# Carrierboard.net
KiCad netlist of a schematic drawn in Altium Designer
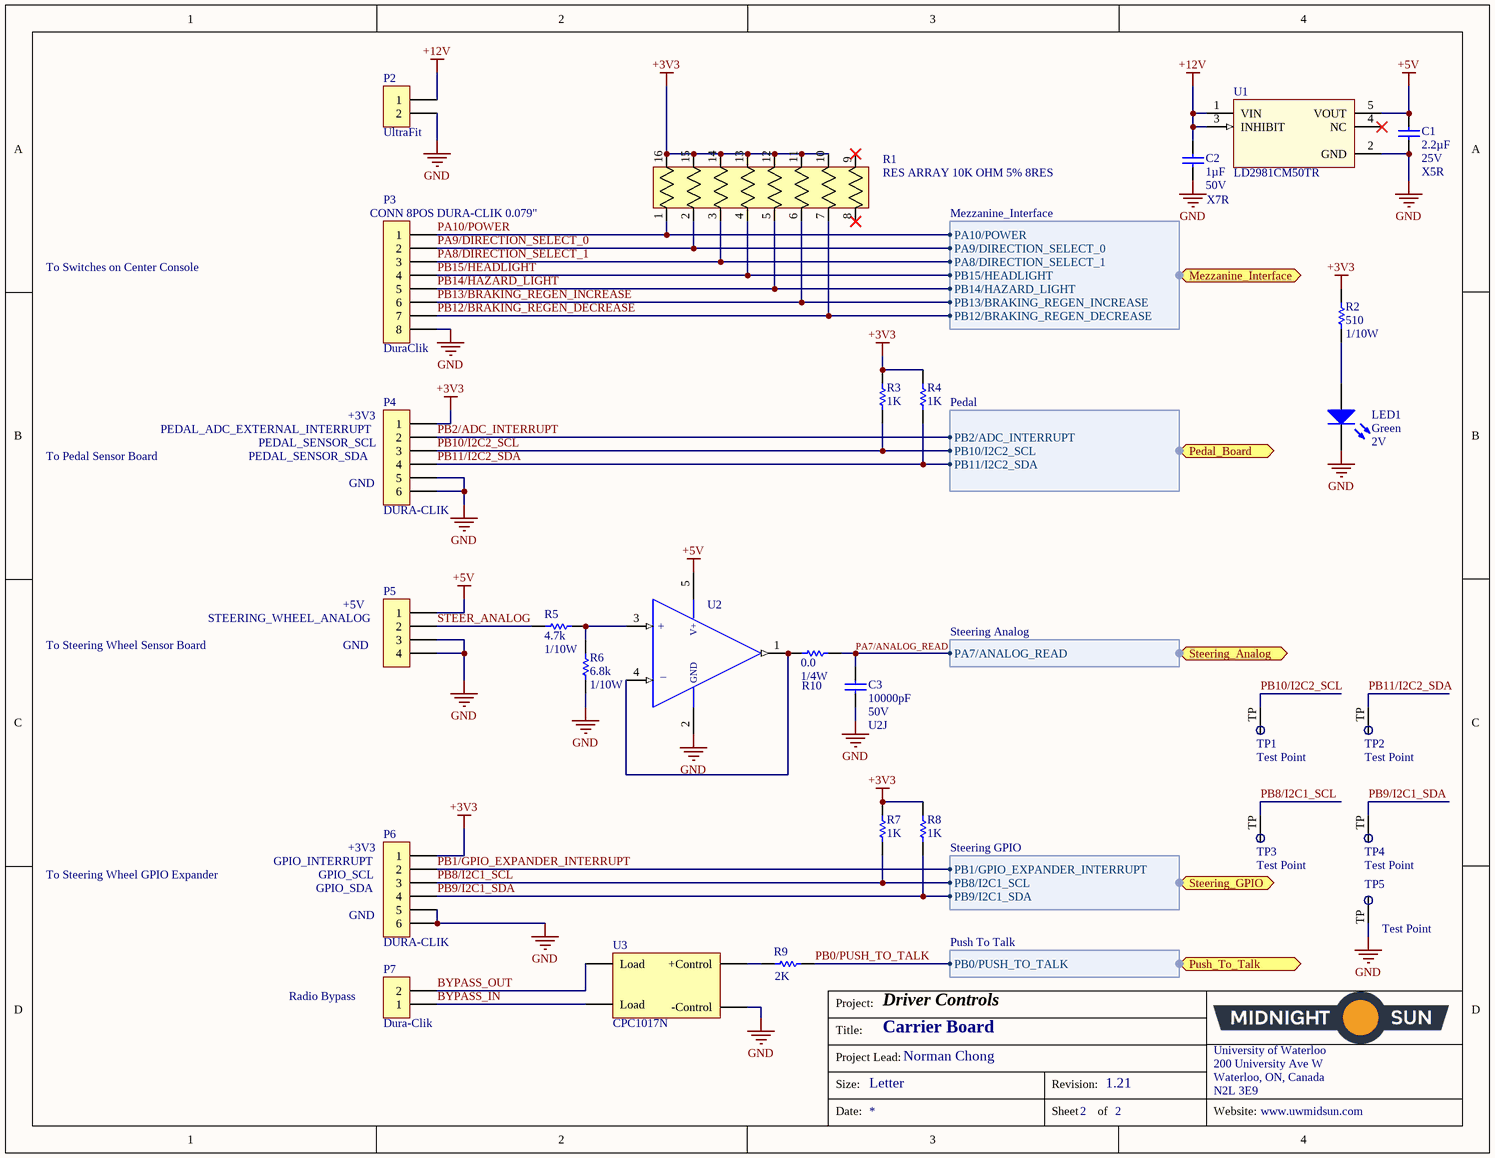
[diagram p0: Carrierboard.SchDoc]

(export (version "E")
  (design (tool "Eeschema 10.0.6"))
  (components
    (comp (ref "C1")
      (value "CAP CER 2.2UF 25V 10% X5R 0603")
      (footprint "CAP, 0603")
      (description "2.2µF ±10% 25V Ceramic Capacitor X5R 0603 (1608 Metric)")
      (fields
        (field (name "TOLERANCE") "±10%")
        (field (name "CAPACITANCE") "2.2µF")
        (field (name "VOLTAGE") "25V")
        (field (name "TEMPERATURE COEFFICIENT") "X5R")
      )
      (libsource (lib "Schematic Diagrams") (part "CAP CER 2.2UF 25V 10% X5R 0603"))
    )
    (comp (ref "C2")
      (value "CAP CER 1UF 50V 10% X7R 0603")
      (footprint "CAP, 0603")
      (description "1µF ±10% 50V Ceramic Capacitor X7R 0603 (1608 Metric)")
      (fields
        (field (name "TOLERANCE") "±10%")
        (field (name "CAPACITANCE") "1µF")
        (field (name "VOLTAGE") "50V")
        (field (name "TEMPERATURE COEFFICIENT") "X7R")
      )
      (libsource (lib "Schematic Diagrams") (part "CAP CER 1UF 50V 10% X7R 0603"))
    )
    (comp (ref "C3")
      (value "CAP CER 10nF 50V 5% X7R 0603")
      (footprint "CAP, 0603")
      (description "10000pF ±5% 50V Ceramic Capacitor U2J 0603 (1608 Metric)")
      (fields
        (field (name "TOLERANCE") "±5%")
        (field (name "CAPACITANCE") "10000pF")
        (field (name "VOLTAGE") "50V")
        (field (name "TEMPERATURE COEFFICIENT") "U2J")
      )
      (libsource (lib "Schematic Diagrams") (part "CAP CER 10nF 50V 5% X7R 0603"))
    )
    (comp (ref "LED1")
      (value "LED GREEN CLEAR 2V 0603")
      (footprint "LED_0603")
      (description "Green 572nm LED Indication - Discrete 2V 0603 (1608 Metric)")
      (fields
        (field (name "MANUFACTURER") "Wurth Electronics Inc.")
        (field (name "MANUFACTURER PART NUMBER") "150060VS75000")
        (field (name "COLOR") "Green")
        (field (name "VOLTAGE - FORWARD (VF) (TYP)") "2V")
      )
      (libsource (lib "Schematic Diagrams") (part "LED GREEN CLEAR 2V 0603"))
    )
    (comp (ref "P2")
      (value "CONN 2POS ULTRA-FIT 0.138\"")
      (footprint "CONN, 2POS ULTRA-FIT")
      (description "2 Positions Header, Shrouded Connector 0.138\" (3.50mm) Through Hole Gold")
      (fields (field (name "VOLTAGE") "400V") (field (name "SERIES") "UltraFit"))
      (libsource (lib "Schematic Diagrams") (part "CONN 2POS ULTRA-FIT 0.138{dblquote}"))
    )
    (comp (ref "P3")
      (value "CONN 8POS DURA-CLIK 0.079\"")
      (footprint "CONN, 8POS Dura-Clik")
      (description "8 Positions Header Connector 0.079\" (2.00mm) Surface Mount Tin")
      (fields (field (name "SERIES") "DuraClik"))
      (libsource (lib "Schematic Diagrams") (part "CONN 8POS DURA-CLIK 0.079{dblquote}"))
    )
    (comp (ref "P4")
      (value "DURA-CLIK")
      (footprint "CONN, 6POS DURA-CLIK VERT")
      (description "6 Positions Header, Shrouded Connector 0.079\" (2.00mm) Surface Mount, Vertical Tin")
      (fields (field (name "MANUFACTURER") "Molex") (field (name "MANUFACTURER PART NUMBER") "5600200820"))
      (libsource (lib "Schematic Diagrams") (part "CONN 6POS DURA-CLIK 0.079{dblquote}"))
    )
    (comp (ref "P5")
      (value "Dura-Clik")
      (footprint "CONN, 4POS DURA-CLIK VERT")
      (description "4 Positions Header Connector 0.079\" (2.00mm) Surface Mount Tin")
      (fields
        (field (name "MANUFACTURER") "Molex, LLC")
        (field (name "MANUFACTURER PART NUMBER") "5600200420")
      )
      (libsource (lib "Schematic Diagrams") (part "CONN 4POS DURA-CLIK 0.079{dblquote}"))
    )
    (comp (ref "P6")
      (value "DURA-CLIK")
      (footprint "CONN, 6POS DURA-CLIK VERT")
      (description "6 Positions Header, Shrouded Connector 0.079\" (2.00mm) Surface Mount, Vertical Tin")
      (fields (field (name "MANUFACTURER") "Molex") (field (name "MANUFACTURER PART NUMBER") "5600200820"))
      (libsource (lib "Schematic Diagrams") (part "CONN 6POS DURA-CLIK 0.079{dblquote}"))
    )
    (comp (ref "P7")
      (value "Dura-Clik")
      (footprint "CONN, 2POS Dura-Click Vertical")
      (description "2 Positions Header, Shrouded Connector 0.079\" (2.00mm) Surface Mount, Vertical Tin")
      (fields
        (field (name "MANUFACTURER") "Molex, LLC")
        (field (name "MANUFACTURER PART NUMBER") "5600200220")
      )
      (libsource (lib "Schematic Diagrams") (part "CONN 2POS DURA-CLIK 0.079{dblquote} VERT"))
    )
    (comp (ref "R1")
      (value "RES ARRAY 10K OHM 5% 8RES")
      (footprint "RES ARRAY, 8 POS 1506")
      (description "RES ARRAY SMD 10K 5% 62.5mW 1506")
      (fields
        (field (name "MANUFACTURER_PART_NUMBER") "EXB-2HV103JV")
        (field (name "MANUFACTURER") "Panasonic Electronic Components")
        (field (name "COPYRIGHT") "Copyright (C) 2015 Accelerated Designs. All rights reserved")
      )
      (libsource (lib "Schematic Diagrams") (part "RES ARRAY 10K OHM 5% 8RES EXB-2HV103JV"))
    )
    (comp (ref "R2")
      (value "RES 510 OHM 5% 1/10W 0603")
      (footprint "RES, 0603")
      (description "RES SMD 510 OHM 5% 1/10W 0603")
      (fields
        (field (name "TOLERANCE") "±5%")
        (field (name "RESISTANCE") "510")
        (field (name "POWER") "1/10W")
      )
      (libsource (lib "Schematic Diagrams") (part "RES 510 OHM 5% 1/10W 0603"))
    )
    (comp (ref "R3")
      (value "1K")
      (footprint "RES, 0603")
      (description "1k Ohm ±5% 0.1W, 1/10W Chip Resistor 0603 (1608 Metric)")
      (fields
        (field (name "MANUFACTURER") "Yageo")
        (field (name "MANUFACTURER PART NUMBER") "RC0603JR-071KL")
      )
      (libsource (lib "Schematic Diagrams") (part "RES 1K OHM 5% 1/10W 0603"))
    )
    (comp (ref "R4")
      (value "1K")
      (footprint "RES, 0603")
      (description "1k Ohm ±5% 0.1W, 1/10W Chip Resistor 0603 (1608 Metric)")
      (fields
        (field (name "MANUFACTURER") "Yageo")
        (field (name "MANUFACTURER PART NUMBER") "RC0603JR-071KL")
      )
      (libsource (lib "Schematic Diagrams") (part "RES 1K OHM 5% 1/10W 0603"))
    )
    (comp (ref "R5")
      (value "RES 4.7K OHM 1% 1/10W 0603")
      (footprint "RES, 0603")
      (description "4.7k Ohm ±1% 0.1W, 1/10W Chip Resistor 0603 (1608 Metric) Moisture Resistant Thick Film")
      (fields
        (field (name "TOLERANCE") "±1%")
        (field (name "RESISTANCE (OHMS)") "4.7k")
        (field (name "POWER (WATTS)") "1/10W")
      )
      (libsource (lib "Schematic Diagrams") (part "RES 4.7K OHM 1% 1/10W 0603"))
    )
    (comp (ref "R6")
      (value "RES 6.8k OHM 1% 1/10W 0603")
      (footprint "RES, 0603")
      (description "RES SMD 6.8K OHM 1% 1/10W 0603")
      (fields
        (field (name "TOLERANCE") "±1%")
        (field (name "RESISTANCE") "6.8k")
        (field (name "POWER") "1/10W")
      )
      (libsource (lib "Schematic Diagrams") (part "RES 6.8k OHM 1% 1/10W 0603"))
    )
    (comp (ref "R7")
      (value "1K")
      (footprint "RES, 0603")
      (description "1k Ohm ±5% 0.1W, 1/10W Chip Resistor 0603 (1608 Metric)")
      (fields
        (field (name "MANUFACTURER") "Yageo")
        (field (name "MANUFACTURER PART NUMBER") "RC0603JR-071KL")
      )
      (libsource (lib "Schematic Diagrams") (part "RES 1K OHM 5% 1/10W 0603"))
    )
    (comp (ref "R8")
      (value "1K")
      (footprint "RES, 0603")
      (description "1k Ohm ±5% 0.1W, 1/10W Chip Resistor 0603 (1608 Metric)")
      (fields
        (field (name "MANUFACTURER") "Yageo")
        (field (name "MANUFACTURER PART NUMBER") "RC0603JR-071KL")
      )
      (libsource (lib "Schematic Diagrams") (part "RES 1K OHM 5% 1/10W 0603"))
    )
    (comp (ref "R9")
      (value "2K")
      (footprint "RES, 0603")
      (description "2k Ohm ±1% 0.1W, 1/10W Chip Resistor 0603 (1608 Metric) Moisture Resistant Thick Film")
      (fields
        (field (name "MANUFACTURER") "Yageo")
        (field (name "MANUFACTURER PART NUMBER") "RC0603FR-072KL")
      )
      (libsource (lib "Schematic Diagrams") (part "RES 2K OHM 1% 1/10W 0603"))
    )
    (comp (ref "R10")
      (value "RES 0.0 OHM 1/4W 0603")
      (footprint "RES, 0603")
      (description "RES SMD 0.0 OHM JUMPER 1/4W 0603")
      (fields (field (name "RESISTANCE") "0.0") (field (name "POWER (WATTS)") "1/4W"))
      (libsource (lib "Schematic Diagrams") (part "RES 0.0 OHM 1/4W 0603"))
    )
    (comp (ref "TP1")
      (value "Test Point")
      (footprint "Test Point")
      (libsource (lib "Schematic Diagrams") (part "Test Point"))
    )
    (comp (ref "TP2")
      (value "Test Point")
      (footprint "Test Point")
      (libsource (lib "Schematic Diagrams") (part "Test Point"))
    )
    (comp (ref "TP3")
      (value "Test Point")
      (footprint "Test Point")
      (libsource (lib "Schematic Diagrams") (part "Test Point"))
    )
    (comp (ref "TP4")
      (value "Test Point")
      (footprint "Test Point")
      (libsource (lib "Schematic Diagrams") (part "Test Point"))
    )
    (comp (ref "TP5")
      (value "Test Point")
      (footprint "Test Point")
      (libsource (lib "Schematic Diagrams") (part "Test Point"))
    )
    (comp (ref "U1")
      (value "IC REG LDO 5V 0.1A SOT23-5")
      (footprint "SOT95P280X145-5N")
      (description "Linear Voltage Regulator IC Positive Fixed Output 5V 100mA SOT-23-5")
      (fields (field (name "MANUFACTURER PART NUMBER 1") "LD2981CM50TR"))
      (libsource (lib "Schematic Diagrams") (part "IC REG LDO 5V 0.1A SOT23-5"))
    )
    (comp (ref "U2")
      (value "IC OP AMP GEN PURPOSE RR 10MHZ SOT-23-5")
      (footprint "IC OP AMP GP RR 10MHZ SOT-23-5")
      (description "General Purpose Amplifier 1 Circuit Rail-to-Rail SOT-23-5")
      (libsource (lib "Schematic Diagrams") (part "IC OP AMP GEN PURPOSE RR 10MHZ SOT-23-5"))
    )
    (comp (ref "U3")
      (value "CPC1017N")
      (footprint "RELAY SOP4")
      (description "Relay Solid-State SPST-NO 4-SOP")
      (fields
        (field (name "MANUFACTURER") "IXYS Integrated Circuits Division")
        (field (name "MANUFACTURER PART NUMBER") "CPC1017NTR")
      )
      (libsource (lib "Schematic Diagrams") (part "RELAY CPC1017N SPST 100mA"))
    )
  )
  (nets
    (net (code "9") (name "+3V3") (class "Default")
      (node (ref "P4") (pin "1") (pinfunction "1_1") (pintype "passive"))
      (node (ref "P6") (pin "1") (pinfunction "1_1") (pintype "passive"))
      (node (ref "R1") (pin "10") (pinfunction "10_10") (pintype "passive"))
      (node (ref "R1") (pin "11") (pinfunction "11_11") (pintype "passive"))
      (node (ref "R1") (pin "12") (pinfunction "12_12") (pintype "passive"))
      (node (ref "R1") (pin "13") (pinfunction "13_13") (pintype "passive"))
      (node (ref "R1") (pin "14") (pinfunction "14_14") (pintype "passive"))
      (node (ref "R1") (pin "15") (pinfunction "15_15") (pintype "passive"))
      (node (ref "R1") (pin "16") (pinfunction "16_16") (pintype "passive"))
      (node (ref "R2") (pin "1") (pinfunction "1_1") (pintype "passive"))
      (node (ref "R3") (pin "1") (pinfunction "1_1") (pintype "passive"))
      (node (ref "R4") (pin "1") (pinfunction "1_1") (pintype "passive"))
      (node (ref "R7") (pin "1") (pinfunction "1_1") (pintype "passive"))
      (node (ref "R8") (pin "1") (pinfunction "1_1") (pintype "passive"))
    )
    (net (code "10") (name "+5V") (class "Default")
      (node (ref "C1") (pin "1") (pinfunction "1_1") (pintype "passive"))
      (node (ref "P5") (pin "1") (pinfunction "1_1") (pintype "passive"))
      (node (ref "U1") (pin "5") (pinfunction "VOUT_5") (pintype "power_in"))
      (node (ref "U2") (pin "5") (pinfunction "VDD_5") (pintype "power_in"))
    )
    (net (code "11") (name "+12V") (class "Default")
      (node (ref "C2") (pin "1") (pinfunction "1_1") (pintype "passive"))
      (node (ref "P2") (pin "1") (pinfunction "1_1") (pintype "passive"))
      (node (ref "U1") (pin "1") (pinfunction "VIN_1") (pintype "power_in"))
      (node (ref "U1") (pin "3") (pinfunction "INHIBIT_3") (pintype "input"))
    )
    (net (code "12") (name "/BYPASS_IN") (class "Default")
      (node (ref "P7") (pin "1") (pinfunction "1_1") (pintype "passive"))
      (node (ref "U3") (pin "3") (pinfunction "Load_3") (pintype "passive"))
    )
    (net (code "13") (name "/BYPASS_OUT") (class "Default")
      (node (ref "P7") (pin "2") (pinfunction "2_2") (pintype "passive"))
      (node (ref "U3") (pin "4") (pinfunction "Load_4") (pintype "passive"))
    )
    (net (code "14") (name "/PA7{slash}ANALOG_READ") (class "Default")
      (node (ref "C3") (pin "1") (pinfunction "1_1") (pintype "passive"))
      (node (ref "R10") (pin "2") (pinfunction "2_2") (pintype "passive"))
    )
    (net (code "15") (name "/PA8{slash}DIRECTION_SELECT_1") (class "Default")
      (node (ref "P3") (pin "3") (pinfunction "3_3") (pintype "passive"))
      (node (ref "R1") (pin "3") (pinfunction "3_3") (pintype "passive"))
    )
    (net (code "16") (name "/PA9{slash}DIRECTION_SELECT_0") (class "Default")
      (node (ref "P3") (pin "2") (pinfunction "2_2") (pintype "passive"))
      (node (ref "R1") (pin "2") (pinfunction "2_2") (pintype "passive"))
    )
    (net (code "17") (name "/PA10{slash}POWER") (class "Default")
      (node (ref "P3") (pin "1") (pinfunction "1_1") (pintype "passive"))
      (node (ref "R1") (pin "1") (pinfunction "1_1") (pintype "passive"))
    )
    (net (code "18") (name "/PB0{slash}PUSH_TO_TALK") (class "Default")
      (node (ref "R9") (pin "2") (pinfunction "2_2") (pintype "passive"))
    )
    (net (code "19") (name "/PB1{slash}GPIO_EXPANDER_INTERRUPT") (class "Default")
      (node (ref "P6") (pin "2") (pinfunction "2_2") (pintype "passive"))
    )
    (net (code "20") (name "/PB2{slash}ADC_INTERRUPT") (class "Default")
      (node (ref "P4") (pin "2") (pinfunction "2_2") (pintype "passive"))
    )
    (net (code "21") (name "/PB8{slash}I2C1_SCL") (class "Default")
      (node (ref "P6") (pin "3") (pinfunction "3_3") (pintype "passive"))
      (node (ref "R7") (pin "2") (pinfunction "2_2") (pintype "passive"))
      (node (ref "TP3") (pin "TP") (pinfunction "1_TP") (pintype "passive"))
    )
    (net (code "22") (name "/PB9{slash}I2C1_SDA") (class "Default")
      (node (ref "P6") (pin "4") (pinfunction "4_4") (pintype "passive"))
      (node (ref "R8") (pin "2") (pinfunction "2_2") (pintype "passive"))
      (node (ref "TP4") (pin "TP") (pinfunction "1_TP") (pintype "passive"))
    )
    (net (code "23") (name "/PB10{slash}I2C2_SCL") (class "Default")
      (node (ref "P4") (pin "3") (pinfunction "3_3") (pintype "passive"))
      (node (ref "R3") (pin "2") (pinfunction "2_2") (pintype "passive"))
      (node (ref "TP1") (pin "TP") (pinfunction "1_TP") (pintype "passive"))
    )
    (net (code "24") (name "/PB11{slash}I2C2_SDA") (class "Default")
      (node (ref "P4") (pin "4") (pinfunction "4_4") (pintype "passive"))
      (node (ref "R4") (pin "2") (pinfunction "2_2") (pintype "passive"))
      (node (ref "TP2") (pin "TP") (pinfunction "1_TP") (pintype "passive"))
    )
    (net (code "25") (name "/PB12{slash}BRAKING_REGEN_DECREASE") (class "Default")
      (node (ref "P3") (pin "7") (pinfunction "7_7") (pintype "passive"))
      (node (ref "R1") (pin "7") (pinfunction "7_7") (pintype "passive"))
    )
    (net (code "26") (name "/PB13{slash}BRAKING_REGEN_INCREASE") (class "Default")
      (node (ref "P3") (pin "6") (pinfunction "6_6") (pintype "passive"))
      (node (ref "R1") (pin "6") (pinfunction "6_6") (pintype "passive"))
    )
    (net (code "27") (name "/PB14{slash}HAZARD_LIGHT") (class "Default")
      (node (ref "P3") (pin "5") (pinfunction "5_5") (pintype "passive"))
      (node (ref "R1") (pin "5") (pinfunction "5_5") (pintype "passive"))
    )
    (net (code "28") (name "/PB15{slash}HEADLIGHT") (class "Default")
      (node (ref "P3") (pin "4") (pinfunction "4_4") (pintype "passive"))
      (node (ref "R1") (pin "4") (pinfunction "4_4") (pintype "passive"))
    )
    (net (code "29") (name "/STEER_ANALOG") (class "Default")
      (node (ref "P5") (pin "2") (pinfunction "2_2") (pintype "passive"))
      (node (ref "R5") (pin "1") (pinfunction "1_1") (pintype "passive"))
    )
    (net (code "35") (name "GND") (class "Default")
      (node (ref "C1") (pin "2") (pinfunction "2_2") (pintype "passive"))
      (node (ref "C2") (pin "2") (pinfunction "2_2") (pintype "passive"))
      (node (ref "C3") (pin "2") (pinfunction "2_2") (pintype "passive"))
      (node (ref "LED1") (pin "2") (pinfunction "K_2") (pintype "passive"))
      (node (ref "P2") (pin "2") (pinfunction "2_2") (pintype "passive"))
      (node (ref "P3") (pin "8") (pinfunction "8_8") (pintype "passive"))
      (node (ref "P4") (pin "5") (pinfunction "5_5") (pintype "passive"))
      (node (ref "P4") (pin "6") (pinfunction "6_6") (pintype "passive"))
      (node (ref "P5") (pin "3") (pinfunction "3_3") (pintype "passive"))
      (node (ref "P5") (pin "4") (pinfunction "4_4") (pintype "passive"))
      (node (ref "P6") (pin "5") (pinfunction "5_5") (pintype "passive"))
      (node (ref "P6") (pin "6") (pinfunction "6_6") (pintype "passive"))
      (node (ref "R6") (pin "2") (pinfunction "2_2") (pintype "passive"))
      (node (ref "TP5") (pin "TP") (pinfunction "1_TP") (pintype "passive"))
      (node (ref "U1") (pin "2") (pinfunction "GND_2") (pintype "power_in"))
      (node (ref "U2") (pin "2") (pinfunction "VSS_2") (pintype "power_in"))
      (node (ref "U3") (pin "2") (pinfunction "-Control_2") (pintype "passive"))
    )
    (net (code "36") (name "Net-(LED1-A)") (class "Default")
      (node (ref "LED1") (pin "1") (pinfunction "A_1") (pintype "passive"))
      (node (ref "R2") (pin "2") (pinfunction "2_2") (pintype "passive"))
    )
    (net (code "37") (name "Net-(U2-+IN)") (class "Default")
      (node (ref "R5") (pin "2") (pinfunction "2_2") (pintype "passive"))
      (node (ref "R6") (pin "1") (pinfunction "1_1") (pintype "passive"))
      (node (ref "U2") (pin "3") (pinfunction "+IN_3") (pintype "input"))
    )
    (net (code "38") (name "Net-(U2--IN)") (class "Default")
      (node (ref "R10") (pin "1") (pinfunction "1_1") (pintype "passive"))
      (node (ref "U2") (pin "1") (pinfunction "OUTPUT_1") (pintype "output"))
      (node (ref "U2") (pin "4") (pinfunction "-IN_4") (pintype "input"))
    )
    (net (code "39") (name "Net-(U3-+Control)") (class "Default")
      (node (ref "R9") (pin "1") (pinfunction "1_1") (pintype "passive"))
      (node (ref "U3") (pin "1") (pinfunction "+Control_1") (pintype "passive"))
    )
    (net (code "40") (name "unconnected-(R1-Pad8)") (class "Default")
      (node (ref "R1") (pin "8") (pinfunction "8_8") (pintype "passive+no_connect"))
    )
    (net (code "41") (name "unconnected-(R1-Pad9)") (class "Default")
      (node (ref "R1") (pin "9") (pinfunction "9_9") (pintype "passive+no_connect"))
    )
    (net (code "42") (name "unconnected-(U1-NC-Pad4)") (class "Default")
      (node (ref "U1") (pin "4") (pinfunction "NC_4") (pintype "passive+no_connect"))
    )
  )
)
